# EDU_High-Speed-Design_CPU_Power.net
KiCad netlist of a schematic drawn in Altium Designer
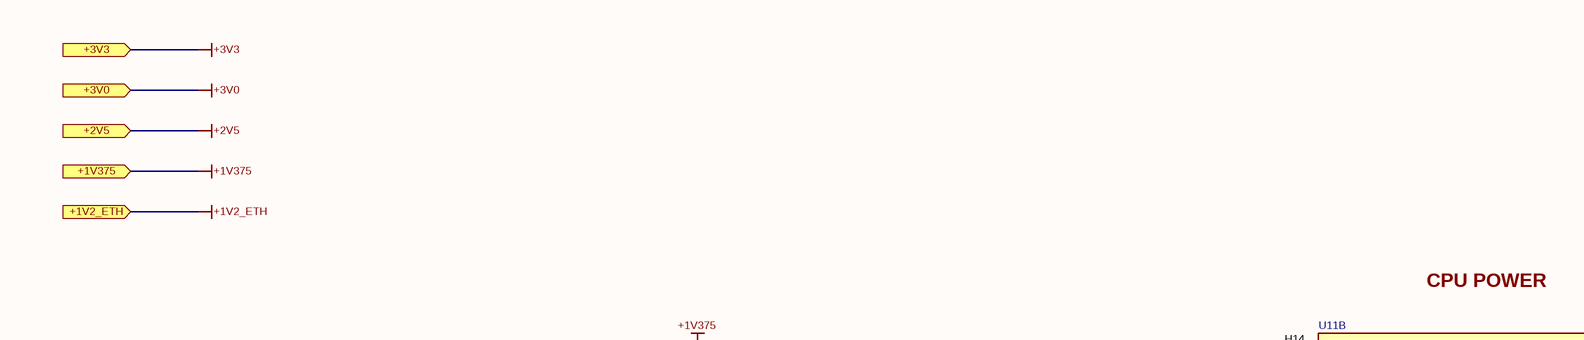
[diagram p0: EDU_High-Speed-Design_CPU_Power.SchDoc, top left]
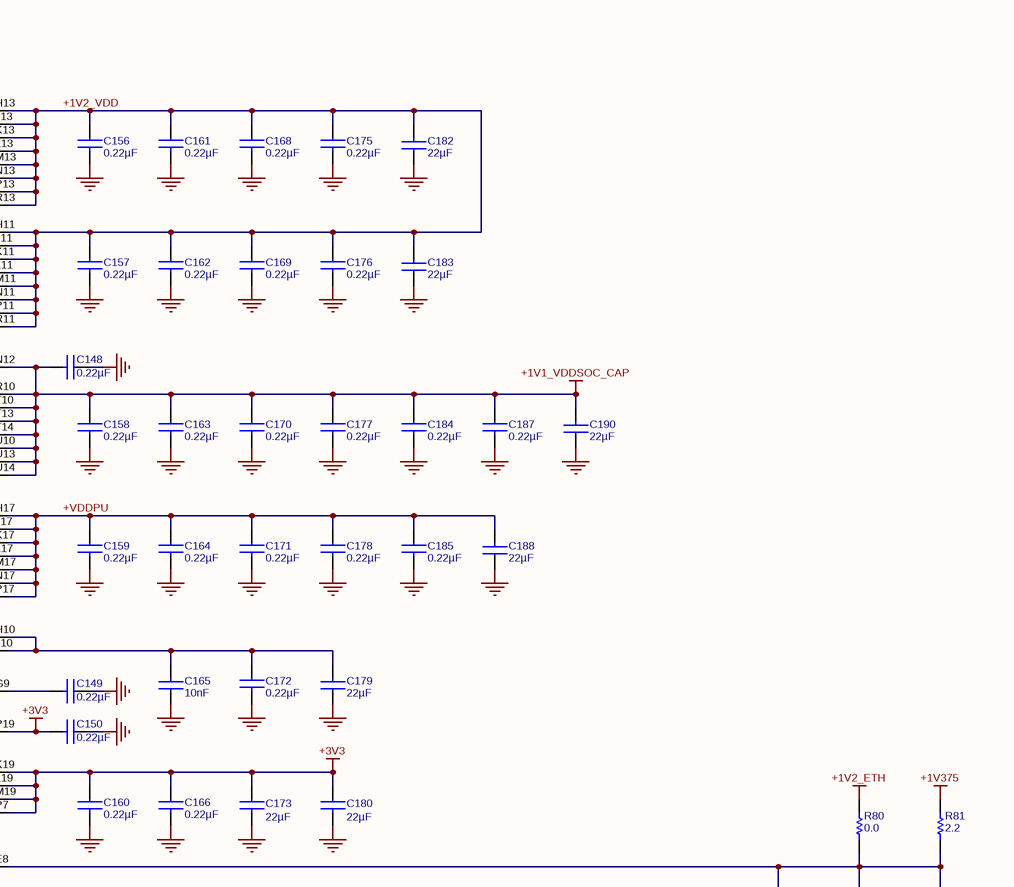
[diagram p1: EDU_High-Speed-Design_CPU_Power.SchDoc, top right]
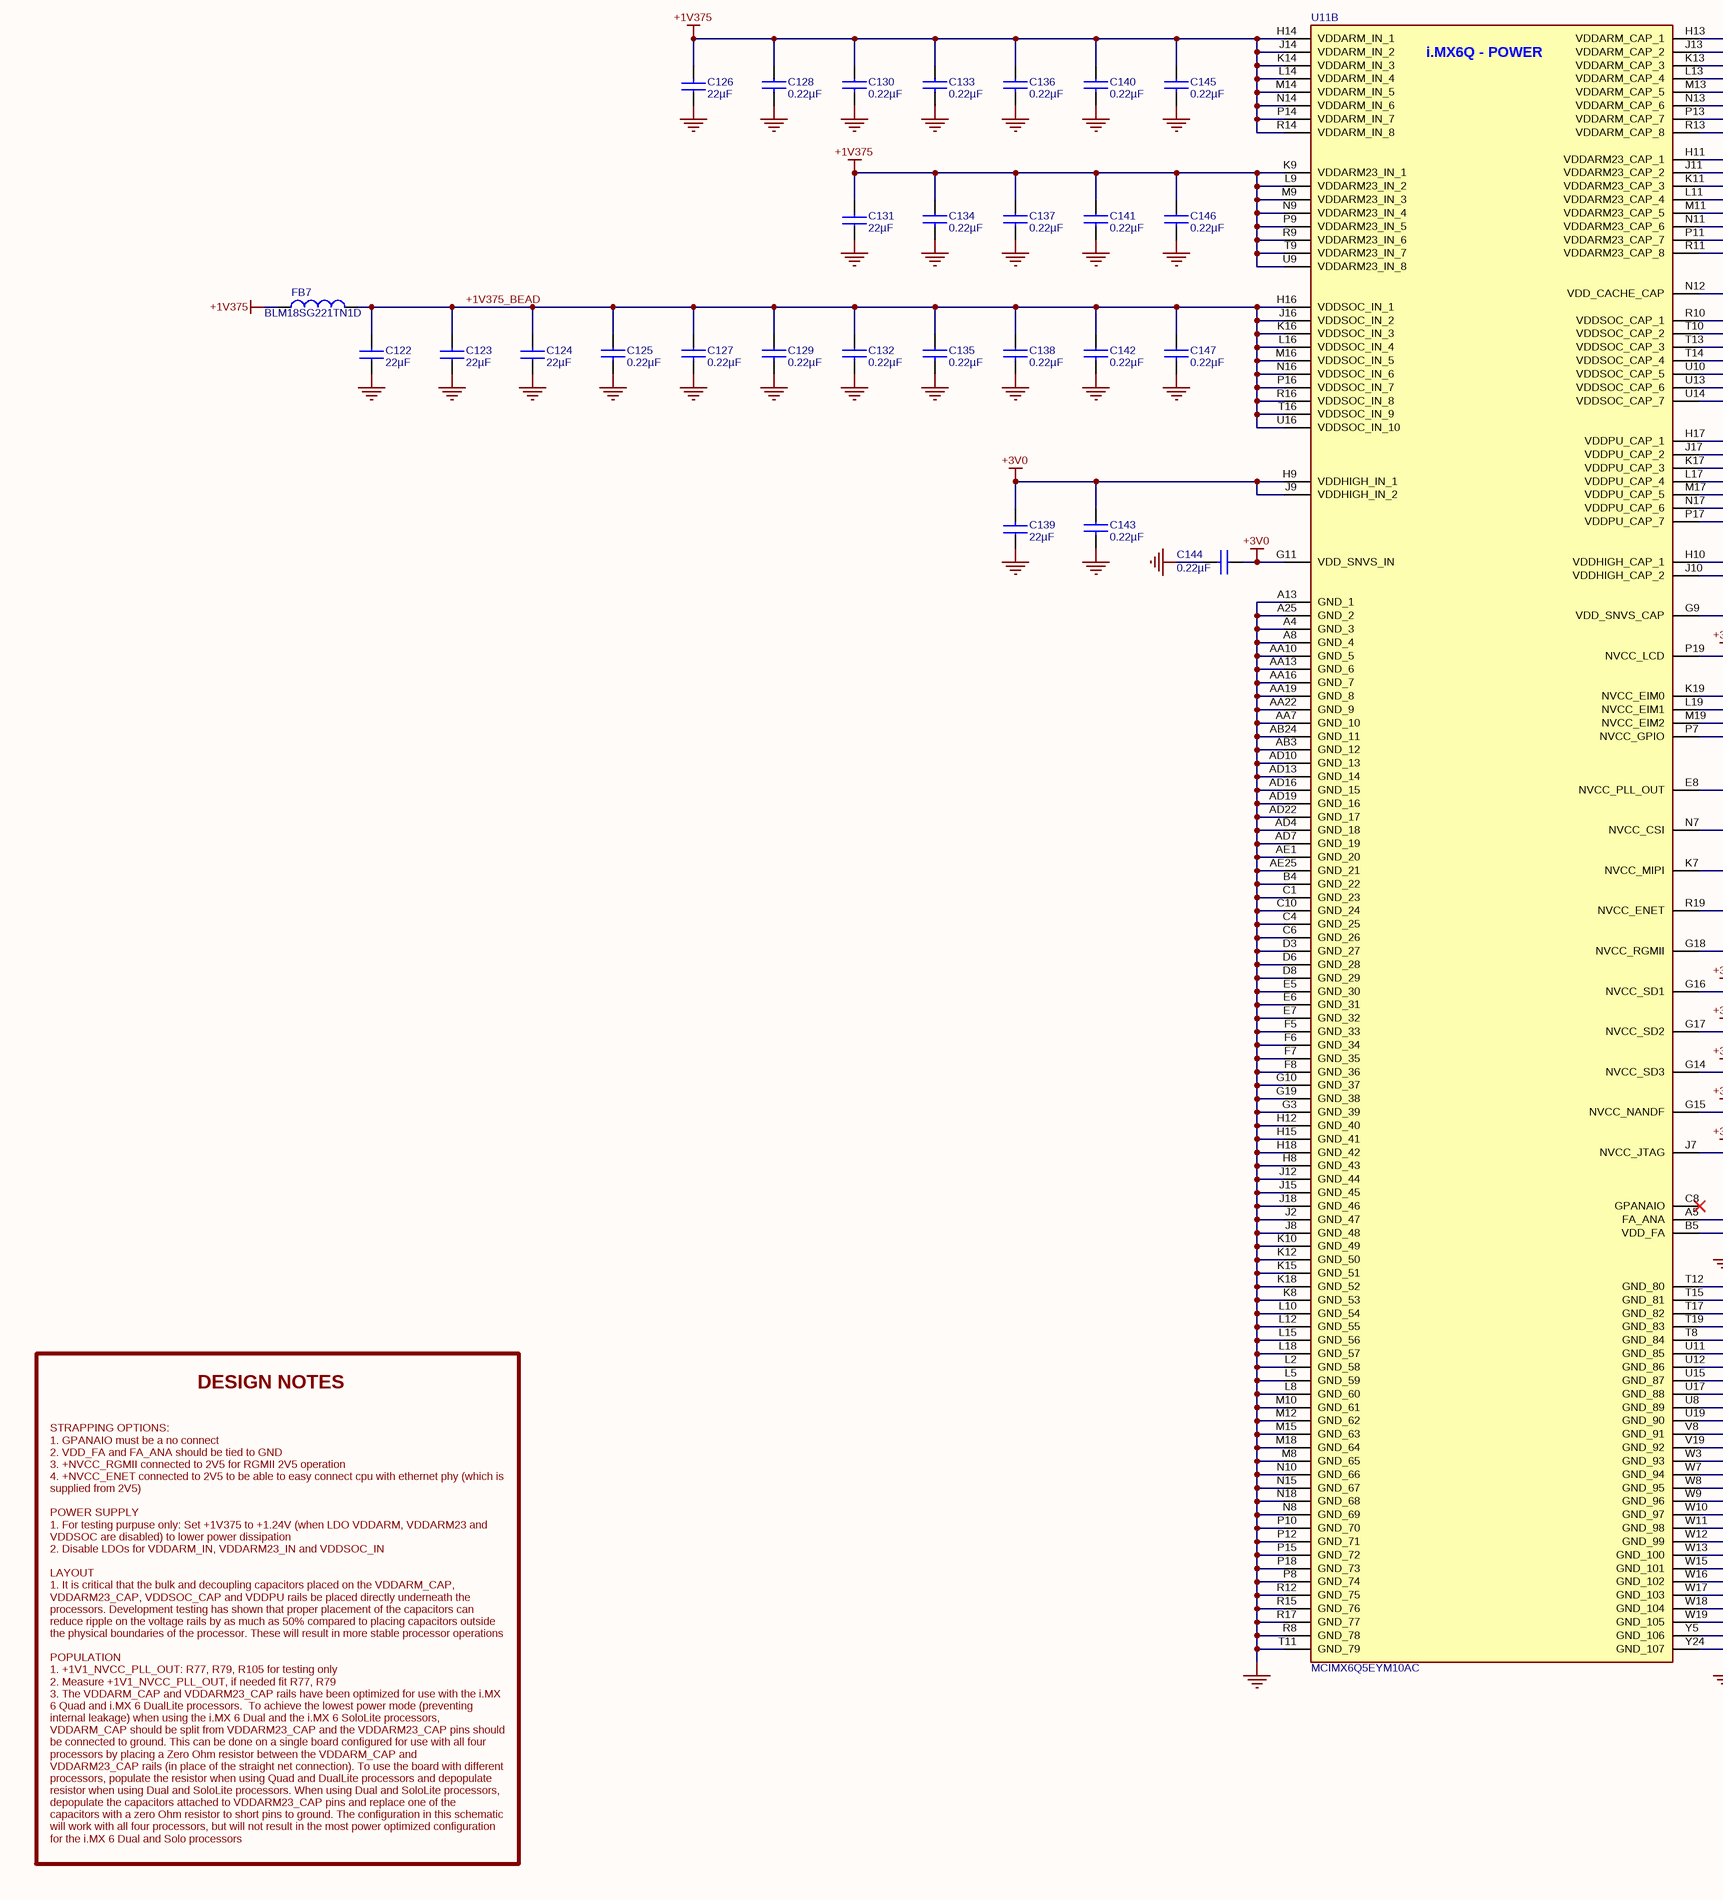
[diagram p2: EDU_High-Speed-Design_CPU_Power.SchDoc, bottom left]
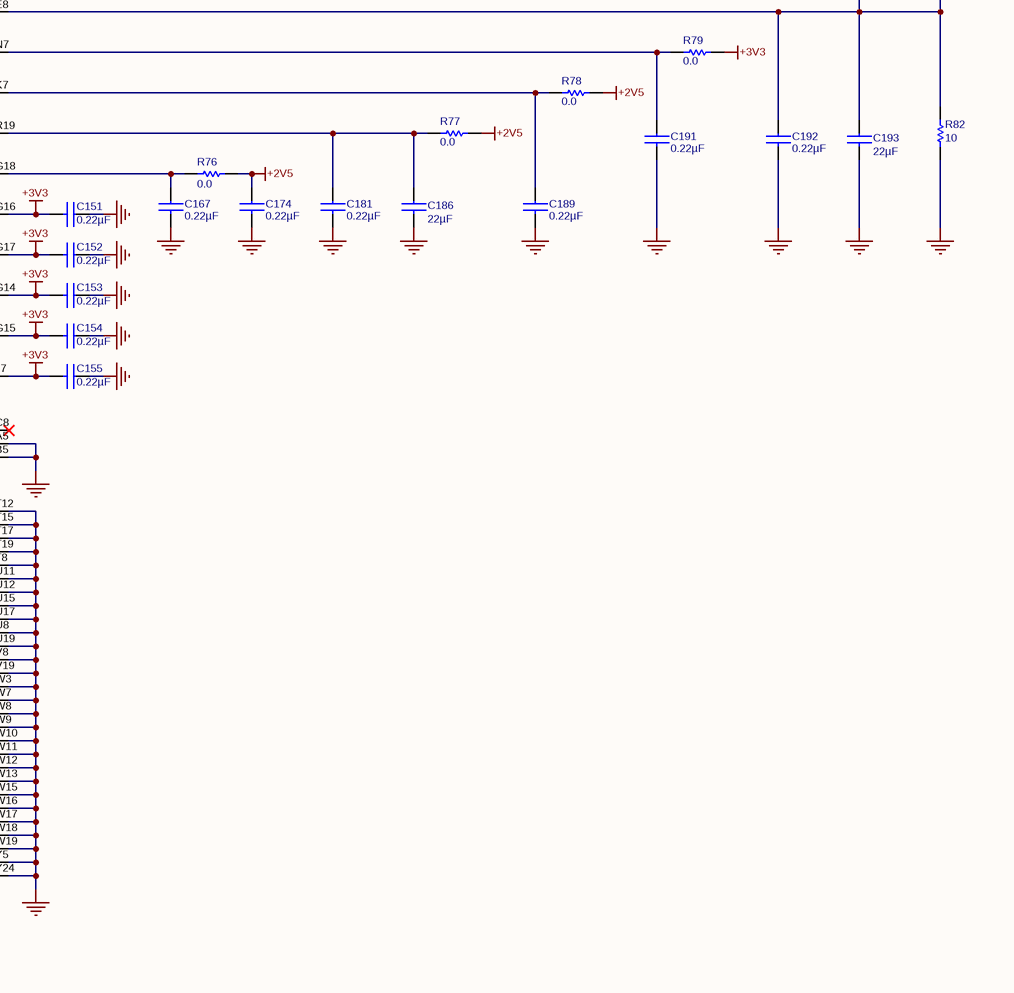
[diagram p3: EDU_High-Speed-Design_CPU_Power.SchDoc, bottom right]

(export (version "E")
  (design (tool "Eeschema 10.0.6"))
  (components
    (comp (ref "C122")
      (value "22µF")
      (footprint "C0603")
      (description "CAP CER 22UF 4V 20% X5R 0603")
      (fields (field (name "VOLTAGE") "4V"))
      (libsource (lib "EDU_High-Speed-Design") (part "GRM188R60G226MEA0L"))
    )
    (comp (ref "C123")
      (value "22µF")
      (footprint "C0603")
      (description "CAP CER 22UF 4V 20% X5R 0603")
      (fields (field (name "VOLTAGE") "4V"))
      (libsource (lib "EDU_High-Speed-Design") (part "GRM188R60G226MEA0L"))
    )
    (comp (ref "C124")
      (value "22µF")
      (footprint "C0603")
      (description "CAP CER 22UF 4V 20% X5R 0603")
      (fields (field (name "VOLTAGE") "4V"))
      (libsource (lib "EDU_High-Speed-Design") (part "GRM188R60G226MEA0L"))
    )
    (comp (ref "C125")
      (value "0.22µF")
      (footprint "C0402")
      (description "CAP CER .22UF 25V X5R 20% 0402")
      (fields (field (name "VOLTAGE") "25V"))
      (libsource (lib "EDU_High-Speed-Design") (part "C1005X5R1E224M"))
    )
    (comp (ref "C126")
      (value "22µF")
      (footprint "C0603")
      (description "CAP CER 22UF 4V 20% X5R 0603")
      (fields (field (name "VOLTAGE") "4V"))
      (libsource (lib "EDU_High-Speed-Design") (part "GRM188R60G226MEA0L"))
    )
    (comp (ref "C127")
      (value "0.22µF")
      (footprint "C0402")
      (description "CAP CER .22UF 25V X5R 20% 0402")
      (fields (field (name "VOLTAGE") "25V"))
      (libsource (lib "EDU_High-Speed-Design") (part "C1005X5R1E224M"))
    )
    (comp (ref "C128")
      (value "0.22µF")
      (footprint "C0402")
      (description "CAP CER .22UF 25V X5R 20% 0402")
      (fields (field (name "VOLTAGE") "25V"))
      (libsource (lib "EDU_High-Speed-Design") (part "C1005X5R1E224M"))
    )
    (comp (ref "C129")
      (value "0.22µF")
      (footprint "C0402")
      (description "CAP CER .22UF 25V X5R 20% 0402")
      (fields (field (name "VOLTAGE") "25V"))
      (libsource (lib "EDU_High-Speed-Design") (part "C1005X5R1E224M"))
    )
    (comp (ref "C130")
      (value "0.22µF")
      (footprint "C0402")
      (description "CAP CER .22UF 25V X5R 20% 0402")
      (fields (field (name "VOLTAGE") "25V"))
      (libsource (lib "EDU_High-Speed-Design") (part "C1005X5R1E224M"))
    )
    (comp (ref "C131")
      (value "22µF")
      (footprint "C0603")
      (description "CAP CER 22UF 4V 20% X5R 0603")
      (fields (field (name "VOLTAGE") "4V"))
      (libsource (lib "EDU_High-Speed-Design") (part "GRM188R60G226MEA0L"))
    )
    (comp (ref "C132")
      (value "0.22µF")
      (footprint "C0402")
      (description "CAP CER .22UF 25V X5R 20% 0402")
      (fields (field (name "VOLTAGE") "25V"))
      (libsource (lib "EDU_High-Speed-Design") (part "C1005X5R1E224M"))
    )
    (comp (ref "C133")
      (value "0.22µF")
      (footprint "C0402")
      (description "CAP CER .22UF 25V X5R 20% 0402")
      (fields (field (name "VOLTAGE") "25V"))
      (libsource (lib "EDU_High-Speed-Design") (part "C1005X5R1E224M"))
    )
    (comp (ref "C134")
      (value "0.22µF")
      (footprint "C0402")
      (description "CAP CER .22UF 25V X5R 20% 0402")
      (fields (field (name "VOLTAGE") "25V"))
      (libsource (lib "EDU_High-Speed-Design") (part "C1005X5R1E224M"))
    )
    (comp (ref "C135")
      (value "0.22µF")
      (footprint "C0402")
      (description "CAP CER .22UF 25V X5R 20% 0402")
      (fields (field (name "VOLTAGE") "25V"))
      (libsource (lib "EDU_High-Speed-Design") (part "C1005X5R1E224M"))
    )
    (comp (ref "C136")
      (value "0.22µF")
      (footprint "C0402")
      (description "CAP CER .22UF 25V X5R 20% 0402")
      (fields (field (name "VOLTAGE") "25V"))
      (libsource (lib "EDU_High-Speed-Design") (part "C1005X5R1E224M"))
    )
    (comp (ref "C137")
      (value "0.22µF")
      (footprint "C0402")
      (description "CAP CER .22UF 25V X5R 20% 0402")
      (fields (field (name "VOLTAGE") "25V"))
      (libsource (lib "EDU_High-Speed-Design") (part "C1005X5R1E224M"))
    )
    (comp (ref "C138")
      (value "0.22µF")
      (footprint "C0402")
      (description "CAP CER .22UF 25V X5R 20% 0402")
      (fields (field (name "VOLTAGE") "25V"))
      (libsource (lib "EDU_High-Speed-Design") (part "C1005X5R1E224M"))
    )
    (comp (ref "C139")
      (value "22µF")
      (footprint "C0603")
      (description "CAP CER 22UF 4V 20% X5R 0603")
      (fields (field (name "VOLTAGE") "4V"))
      (libsource (lib "EDU_High-Speed-Design") (part "GRM188R60G226MEA0L"))
    )
    (comp (ref "C140")
      (value "0.22µF")
      (footprint "C0402")
      (description "CAP CER .22UF 25V X5R 20% 0402")
      (fields (field (name "VOLTAGE") "25V"))
      (libsource (lib "EDU_High-Speed-Design") (part "C1005X5R1E224M"))
    )
    (comp (ref "C141")
      (value "0.22µF")
      (footprint "C0402")
      (description "CAP CER .22UF 25V X5R 20% 0402")
      (fields (field (name "VOLTAGE") "25V"))
      (libsource (lib "EDU_High-Speed-Design") (part "C1005X5R1E224M"))
    )
    (comp (ref "C142")
      (value "0.22µF")
      (footprint "C0402")
      (description "CAP CER .22UF 25V X5R 20% 0402")
      (fields (field (name "VOLTAGE") "25V"))
      (libsource (lib "EDU_High-Speed-Design") (part "C1005X5R1E224M"))
    )
    (comp (ref "C143")
      (value "0.22µF")
      (footprint "C0402")
      (description "CAP CER .22UF 25V X5R 20% 0402")
      (fields (field (name "VOLTAGE") "25V"))
      (libsource (lib "EDU_High-Speed-Design") (part "C1005X5R1E224M"))
    )
    (comp (ref "C144")
      (value "0.22µF")
      (footprint "C0402")
      (description "CAP CER .22UF 25V X5R 20% 0402")
      (fields (field (name "VOLTAGE") "25V"))
      (libsource (lib "EDU_High-Speed-Design") (part "C1005X5R1E224M"))
    )
    (comp (ref "C145")
      (value "0.22µF")
      (footprint "C0402")
      (description "CAP CER .22UF 25V X5R 20% 0402")
      (fields (field (name "VOLTAGE") "25V"))
      (libsource (lib "EDU_High-Speed-Design") (part "C1005X5R1E224M"))
    )
    (comp (ref "C146")
      (value "0.22µF")
      (footprint "C0402")
      (description "CAP CER .22UF 25V X5R 20% 0402")
      (fields (field (name "VOLTAGE") "25V"))
      (libsource (lib "EDU_High-Speed-Design") (part "C1005X5R1E224M"))
    )
    (comp (ref "C147")
      (value "0.22µF")
      (footprint "C0402")
      (description "CAP CER .22UF 25V X5R 20% 0402")
      (fields (field (name "VOLTAGE") "25V"))
      (libsource (lib "EDU_High-Speed-Design") (part "C1005X5R1E224M"))
    )
    (comp (ref "C148")
      (value "0.22µF")
      (footprint "C0402")
      (description "CAP CER .22UF 25V X5R 20% 0402")
      (fields (field (name "VOLTAGE") "25V"))
      (libsource (lib "EDU_High-Speed-Design") (part "C1005X5R1E224M"))
    )
    (comp (ref "C149")
      (value "0.22µF")
      (footprint "C0402")
      (description "CAP CER .22UF 25V X5R 20% 0402")
      (fields (field (name "VOLTAGE") "25V"))
      (libsource (lib "EDU_High-Speed-Design") (part "C1005X5R1E224M"))
    )
    (comp (ref "C150")
      (value "0.22µF")
      (footprint "C0402")
      (description "CAP CER .22UF 25V X5R 20% 0402")
      (fields (field (name "VOLTAGE") "25V"))
      (libsource (lib "EDU_High-Speed-Design") (part "C1005X5R1E224M"))
    )
    (comp (ref "C151")
      (value "0.22µF")
      (footprint "C0402")
      (description "CAP CER .22UF 25V X5R 20% 0402")
      (fields (field (name "VOLTAGE") "25V"))
      (libsource (lib "EDU_High-Speed-Design") (part "C1005X5R1E224M"))
    )
    (comp (ref "C152")
      (value "0.22µF")
      (footprint "C0402")
      (description "CAP CER .22UF 25V X5R 20% 0402")
      (fields (field (name "VOLTAGE") "25V"))
      (libsource (lib "EDU_High-Speed-Design") (part "C1005X5R1E224M"))
    )
    (comp (ref "C153")
      (value "0.22µF")
      (footprint "C0402")
      (description "CAP CER .22UF 25V X5R 20% 0402")
      (fields (field (name "VOLTAGE") "25V"))
      (libsource (lib "EDU_High-Speed-Design") (part "C1005X5R1E224M"))
    )
    (comp (ref "C154")
      (value "0.22µF")
      (footprint "C0402")
      (description "CAP CER .22UF 25V X5R 20% 0402")
      (fields (field (name "VOLTAGE") "25V"))
      (libsource (lib "EDU_High-Speed-Design") (part "C1005X5R1E224M"))
    )
    (comp (ref "C155")
      (value "0.22µF")
      (footprint "C0402")
      (description "CAP CER .22UF 25V X5R 20% 0402")
      (fields (field (name "VOLTAGE") "25V"))
      (libsource (lib "EDU_High-Speed-Design") (part "C1005X5R1E224M"))
    )
    (comp (ref "C156")
      (value "0.22µF")
      (footprint "C0402")
      (description "CAP CER .22UF 25V X5R 20% 0402")
      (fields (field (name "VOLTAGE") "25V"))
      (libsource (lib "EDU_High-Speed-Design") (part "C1005X5R1E224M"))
    )
    (comp (ref "C157")
      (value "0.22µF")
      (footprint "C0402")
      (description "CAP CER .22UF 25V X5R 20% 0402")
      (fields (field (name "VOLTAGE") "25V"))
      (libsource (lib "EDU_High-Speed-Design") (part "C1005X5R1E224M"))
    )
    (comp (ref "C158")
      (value "0.22µF")
      (footprint "C0402")
      (description "CAP CER .22UF 25V X5R 20% 0402")
      (fields (field (name "VOLTAGE") "25V"))
      (libsource (lib "EDU_High-Speed-Design") (part "C1005X5R1E224M"))
    )
    (comp (ref "C159")
      (value "0.22µF")
      (footprint "C0402")
      (description "CAP CER .22UF 25V X5R 20% 0402")
      (fields (field (name "VOLTAGE") "25V"))
      (libsource (lib "EDU_High-Speed-Design") (part "C1005X5R1E224M"))
    )
    (comp (ref "C160")
      (value "0.22µF")
      (footprint "C0402")
      (description "CAP CER .22UF 25V X5R 20% 0402")
      (fields (field (name "VOLTAGE") "25V"))
      (libsource (lib "EDU_High-Speed-Design") (part "C1005X5R1E224M"))
    )
    (comp (ref "C161")
      (value "0.22µF")
      (footprint "C0402")
      (description "CAP CER .22UF 25V X5R 20% 0402")
      (fields (field (name "VOLTAGE") "25V"))
      (libsource (lib "EDU_High-Speed-Design") (part "C1005X5R1E224M"))
    )
    (comp (ref "C162")
      (value "0.22µF")
      (footprint "C0402")
      (description "CAP CER .22UF 25V X5R 20% 0402")
      (fields (field (name "VOLTAGE") "25V"))
      (libsource (lib "EDU_High-Speed-Design") (part "C1005X5R1E224M"))
    )
    (comp (ref "C163")
      (value "0.22µF")
      (footprint "C0402")
      (description "CAP CER .22UF 25V X5R 20% 0402")
      (fields (field (name "VOLTAGE") "25V"))
      (libsource (lib "EDU_High-Speed-Design") (part "C1005X5R1E224M"))
    )
    (comp (ref "C164")
      (value "0.22µF")
      (footprint "C0402")
      (description "CAP CER .22UF 25V X5R 20% 0402")
      (fields (field (name "VOLTAGE") "25V"))
      (libsource (lib "EDU_High-Speed-Design") (part "C1005X5R1E224M"))
    )
    (comp (ref "C165")
      (value "10nF")
      (footprint "C0402")
      (description "CAP CER 10000PF 16V X7R 10% 0402")
      (fields
        (field (name "MANUFACTURER") "TDK Corporation")
        (field (name "MANUFACTURER PART NUMBER") "C1005X7R1C103K")
      )
      (libsource (lib "EDU_High-Speed-Design") (part "C1005X7R1C103K"))
    )
    (comp (ref "C166")
      (value "0.22µF")
      (footprint "C0402")
      (description "CAP CER .22UF 25V X5R 20% 0402")
      (fields (field (name "VOLTAGE") "25V"))
      (libsource (lib "EDU_High-Speed-Design") (part "C1005X5R1E224M"))
    )
    (comp (ref "C167")
      (value "0.22µF")
      (footprint "C0402")
      (description "CAP CER .22UF 25V X5R 20% 0402")
      (fields (field (name "VOLTAGE") "25V"))
      (libsource (lib "EDU_High-Speed-Design") (part "C1005X5R1E224M"))
    )
    (comp (ref "C168")
      (value "0.22µF")
      (footprint "C0402")
      (description "CAP CER .22UF 25V X5R 20% 0402")
      (fields (field (name "VOLTAGE") "25V"))
      (libsource (lib "EDU_High-Speed-Design") (part "C1005X5R1E224M"))
    )
    (comp (ref "C169")
      (value "0.22µF")
      (footprint "C0402")
      (description "CAP CER .22UF 25V X5R 20% 0402")
      (fields (field (name "VOLTAGE") "25V"))
      (libsource (lib "EDU_High-Speed-Design") (part "C1005X5R1E224M"))
    )
    (comp (ref "C170")
      (value "0.22µF")
      (footprint "C0402")
      (description "CAP CER .22UF 25V X5R 20% 0402")
      (fields (field (name "VOLTAGE") "25V"))
      (libsource (lib "EDU_High-Speed-Design") (part "C1005X5R1E224M"))
    )
    (comp (ref "C171")
      (value "0.22µF")
      (footprint "C0402")
      (description "CAP CER .22UF 25V X5R 20% 0402")
      (fields (field (name "VOLTAGE") "25V"))
      (libsource (lib "EDU_High-Speed-Design") (part "C1005X5R1E224M"))
    )
    (comp (ref "C172")
      (value "0.22µF")
      (footprint "C0402")
      (description "CAP CER .22UF 25V X5R 20% 0402")
      (fields (field (name "VOLTAGE") "25V"))
      (libsource (lib "EDU_High-Speed-Design") (part "C1005X5R1E224M"))
    )
    (comp (ref "C173")
      (value "22µF")
      (footprint "C0603")
      (description "CAP CER 22UF 4V 20% X5R 0603")
      (fields (field (name "VOLTAGE") "4V"))
      (libsource (lib "EDU_High-Speed-Design") (part "GRM188R60G226MEA0L"))
    )
    (comp (ref "C174")
      (value "0.22µF")
      (footprint "C0402")
      (description "CAP CER .22UF 25V X5R 20% 0402")
      (fields (field (name "VOLTAGE") "25V"))
      (libsource (lib "EDU_High-Speed-Design") (part "C1005X5R1E224M"))
    )
    (comp (ref "C175")
      (value "0.22µF")
      (footprint "C0402")
      (description "CAP CER .22UF 25V X5R 20% 0402")
      (fields (field (name "VOLTAGE") "25V"))
      (libsource (lib "EDU_High-Speed-Design") (part "C1005X5R1E224M"))
    )
    (comp (ref "C176")
      (value "0.22µF")
      (footprint "C0402")
      (description "CAP CER .22UF 25V X5R 20% 0402")
      (fields (field (name "VOLTAGE") "25V"))
      (libsource (lib "EDU_High-Speed-Design") (part "C1005X5R1E224M"))
    )
    (comp (ref "C177")
      (value "0.22µF")
      (footprint "C0402")
      (description "CAP CER .22UF 25V X5R 20% 0402")
      (fields (field (name "VOLTAGE") "25V"))
      (libsource (lib "EDU_High-Speed-Design") (part "C1005X5R1E224M"))
    )
    (comp (ref "C178")
      (value "0.22µF")
      (footprint "C0402")
      (description "CAP CER .22UF 25V X5R 20% 0402")
      (fields (field (name "VOLTAGE") "25V"))
      (libsource (lib "EDU_High-Speed-Design") (part "C1005X5R1E224M"))
    )
    (comp (ref "C179")
      (value "22µF")
      (footprint "C0603")
      (description "CAP CER 22UF 4V 20% X5R 0603")
      (fields (field (name "VOLTAGE") "4V"))
      (libsource (lib "EDU_High-Speed-Design") (part "GRM188R60G226MEA0L"))
    )
    (comp (ref "C180")
      (value "22µF")
      (footprint "C0603")
      (description "CAP CER 22UF 4V 20% X5R 0603")
      (fields (field (name "VOLTAGE") "4V"))
      (libsource (lib "EDU_High-Speed-Design") (part "GRM188R60G226MEA0L"))
    )
    (comp (ref "C181")
      (value "0.22µF")
      (footprint "C0402")
      (description "CAP CER .22UF 25V X5R 20% 0402")
      (fields (field (name "VOLTAGE") "25V"))
      (libsource (lib "EDU_High-Speed-Design") (part "C1005X5R1E224M"))
    )
    (comp (ref "C182")
      (value "22µF")
      (footprint "C0603")
      (description "CAP CER 22UF 4V 20% X5R 0603")
      (fields (field (name "VOLTAGE") "4V"))
      (libsource (lib "EDU_High-Speed-Design") (part "GRM188R60G226MEA0L"))
    )
    (comp (ref "C183")
      (value "22µF")
      (footprint "C0603")
      (description "CAP CER 22UF 4V 20% X5R 0603")
      (fields (field (name "VOLTAGE") "4V"))
      (libsource (lib "EDU_High-Speed-Design") (part "GRM188R60G226MEA0L"))
    )
    (comp (ref "C184")
      (value "0.22µF")
      (footprint "C0402")
      (description "CAP CER .22UF 25V X5R 20% 0402")
      (fields (field (name "VOLTAGE") "25V"))
      (libsource (lib "EDU_High-Speed-Design") (part "C1005X5R1E224M"))
    )
    (comp (ref "C185")
      (value "0.22µF")
      (footprint "C0402")
      (description "CAP CER .22UF 25V X5R 20% 0402")
      (fields (field (name "VOLTAGE") "25V"))
      (libsource (lib "EDU_High-Speed-Design") (part "C1005X5R1E224M"))
    )
    (comp (ref "C186")
      (value "22µF")
      (footprint "C0603")
      (description "CAP CER 22UF 4V 20% X5R 0603")
      (fields (field (name "VOLTAGE") "4V"))
      (libsource (lib "EDU_High-Speed-Design") (part "GRM188R60G226MEA0L"))
    )
    (comp (ref "C187")
      (value "0.22µF")
      (footprint "C0402")
      (description "CAP CER .22UF 25V X5R 20% 0402")
      (fields (field (name "VOLTAGE") "25V"))
      (libsource (lib "EDU_High-Speed-Design") (part "C1005X5R1E224M"))
    )
    (comp (ref "C188")
      (value "22µF")
      (footprint "C0603")
      (description "CAP CER 22UF 4V 20% X5R 0603")
      (fields (field (name "VOLTAGE") "4V"))
      (libsource (lib "EDU_High-Speed-Design") (part "GRM188R60G226MEA0L"))
    )
    (comp (ref "C189")
      (value "0.22µF")
      (footprint "C0402")
      (description "CAP CER .22UF 25V X5R 20% 0402")
      (fields (field (name "VOLTAGE") "25V"))
      (libsource (lib "EDU_High-Speed-Design") (part "C1005X5R1E224M"))
    )
    (comp (ref "C190")
      (value "22µF")
      (footprint "C0603")
      (description "CAP CER 22UF 4V 20% X5R 0603")
      (fields (field (name "VOLTAGE") "4V"))
      (libsource (lib "EDU_High-Speed-Design") (part "GRM188R60G226MEA0L"))
    )
    (comp (ref "C191")
      (value "0.22µF")
      (footprint "C0402")
      (description "CAP CER .22UF 25V X5R 20% 0402")
      (fields (field (name "VOLTAGE") "25V"))
      (libsource (lib "EDU_High-Speed-Design") (part "C1005X5R1E224M"))
    )
    (comp (ref "C192")
      (value "0.22µF")
      (footprint "C0402")
      (description "CAP CER .22UF 25V X5R 20% 0402")
      (fields (field (name "VOLTAGE") "25V"))
      (libsource (lib "EDU_High-Speed-Design") (part "C1005X5R1E224M"))
    )
    (comp (ref "C193")
      (value "22µF")
      (footprint "C0603")
      (description "CAP CER 22UF 4V 20% X5R 0603")
      (fields (field (name "VOLTAGE") "4V"))
      (libsource (lib "EDU_High-Speed-Design") (part "GRM188R60G226MEA0L"))
    )
    (comp (ref "FB7")
      (value "BLM18SG221TN1D")
      (footprint "L0603")
      (description "FERRITE CHIP 220 OHM 2500MA 0603")
      (libsource (lib "EDU_High-Speed-Design") (part "BLM18SG221TN1D"))
    )
    (comp (ref "R76")
      (value "0.0")
      (footprint "R0402")
      (description "RES 0.0 OHM 1/16W 0402 SMD")
      (libsource (lib "EDU_High-Speed-Design") (part "RC0402JR-070RL"))
    )
    (comp (ref "R77")
      (value "0.0")
      (footprint "R0402")
      (description "RES 0.0 OHM 1/16W 0402 SMD")
      (libsource (lib "EDU_High-Speed-Design") (part "RC0402JR-070RL"))
    )
    (comp (ref "R78")
      (value "0.0")
      (footprint "R0402")
      (description "RES 0.0 OHM 1/16W 0402 SMD")
      (libsource (lib "EDU_High-Speed-Design") (part "RC0402JR-070RL"))
    )
    (comp (ref "R79")
      (value "0.0")
      (footprint "R0402")
      (description "RES 0.0 OHM 1/16W 0402 SMD")
      (libsource (lib "EDU_High-Speed-Design") (part "RC0402JR-070RL"))
    )
    (comp (ref "R80")
      (value "0.0")
      (footprint "R0402")
      (description "RES 0.0 OHM 1/16W 0402 SMD")
      (libsource (lib "EDU_High-Speed-Design") (part "RC0402JR-070RL"))
    )
    (comp (ref "R81")
      (value "2.2")
      (footprint "R0402")
      (description "RES 2.20 OHM 1/16W 1% 0402 SMD")
      (libsource (lib "EDU_High-Speed-Design") (part "CRCW04022R20FKED"))
    )
    (comp (ref "R82")
      (value "10")
      (footprint "R0402")
      (description "RES 10.0 OHM 1/16W 1% 0402 SMD")
      (libsource (lib "EDU_High-Speed-Design") (part "RC0402FR-0710RL"))
    )
    (comp (ref "U11")
      (value "MCIMX6Q5EYM10AC")
      (footprint "MCIMX6Q5EYM10AC")
      (description "IC MCU 32BIT ARM QUAD 624FCBGA")
      (libsource (lib "EDU_High-Speed-Design") (part "MCIMX6Q5EYM10AC"))
    )
  )
  (nets
    (net (code "1") (name "+1V1_VDDSOC_CAP") (class "Default")
      (node (ref "C148") (pin "2") (pinfunction "2_2") (pintype "passive"))
      (node (ref "C158") (pin "1") (pinfunction "1_1") (pintype "passive"))
      (node (ref "C163") (pin "1") (pinfunction "1_1") (pintype "passive"))
      (node (ref "C170") (pin "1") (pinfunction "1_1") (pintype "passive"))
      (node (ref "C177") (pin "1") (pinfunction "1_1") (pintype "passive"))
      (node (ref "C184") (pin "1") (pinfunction "1_1") (pintype "passive"))
      (node (ref "C187") (pin "1") (pinfunction "1_1") (pintype "passive"))
      (node (ref "C190") (pin "2") (pinfunction "2_2") (pintype "passive"))
      (node (ref "U11") (pin "N12") (pinfunction "VDD_CACHE_CAP_N12") (pintype "passive"))
      (node (ref "U11") (pin "R10") (pinfunction "VDDSOC_CAP_1_R10") (pintype "passive"))
      (node (ref "U11") (pin "T10") (pinfunction "VDDSOC_CAP_2_T10") (pintype "passive"))
      (node (ref "U11") (pin "T13") (pinfunction "VDDSOC_CAP_3_T13") (pintype "passive"))
      (node (ref "U11") (pin "T14") (pinfunction "VDDSOC_CAP_4_T14") (pintype "passive"))
      (node (ref "U11") (pin "U10") (pinfunction "VDDSOC_CAP_5_U10") (pintype "passive"))
      (node (ref "U11") (pin "U13") (pinfunction "VDDSOC_CAP_6_U13") (pintype "passive"))
      (node (ref "U11") (pin "U14") (pinfunction "VDDSOC_CAP_7_U14") (pintype "passive"))
    )
    (net (code "2") (name "+1V2_ETH") (class "Default")
      (node (ref "R80") (pin "1") (pinfunction "1_1") (pintype "passive"))
    )
    (net (code "3") (name "+1V375") (class "Default")
      (node (ref "C126") (pin "2") (pinfunction "2_2") (pintype "passive"))
      (node (ref "C128") (pin "1") (pinfunction "1_1") (pintype "passive"))
      (node (ref "C130") (pin "1") (pinfunction "1_1") (pintype "passive"))
      (node (ref "C131") (pin "2") (pinfunction "2_2") (pintype "passive"))
      (node (ref "C133") (pin "1") (pinfunction "1_1") (pintype "passive"))
      (node (ref "C134") (pin "1") (pinfunction "1_1") (pintype "passive"))
      (node (ref "C136") (pin "1") (pinfunction "1_1") (pintype "passive"))
      (node (ref "C137") (pin "1") (pinfunction "1_1") (pintype "passive"))
      (node (ref "C140") (pin "1") (pinfunction "1_1") (pintype "passive"))
      (node (ref "C141") (pin "1") (pinfunction "1_1") (pintype "passive"))
      (node (ref "C145") (pin "1") (pinfunction "1_1") (pintype "passive"))
      (node (ref "C146") (pin "1") (pinfunction "1_1") (pintype "passive"))
      (node (ref "FB7") (pin "1") (pinfunction "1_1") (pintype "passive"))
      (node (ref "R81") (pin "2") (pinfunction "2_2") (pintype "passive"))
      (node (ref "U11") (pin "H14") (pinfunction "VDDARM_IN_1_H14") (pintype "passive"))
      (node (ref "U11") (pin "J14") (pinfunction "VDDARM_IN_2_J14") (pintype "passive"))
      (node (ref "U11") (pin "K14") (pinfunction "VDDARM_IN_3_K14") (pintype "passive"))
      (node (ref "U11") (pin "K9") (pinfunction "VDDARM23_IN_1_K9") (pintype "passive"))
      (node (ref "U11") (pin "L14") (pinfunction "VDDARM_IN_4_L14") (pintype "passive"))
      (node (ref "U11") (pin "L9") (pinfunction "VDDARM23_IN_2_L9") (pintype "passive"))
      (node (ref "U11") (pin "M14") (pinfunction "VDDARM_IN_5_M14") (pintype "passive"))
      (node (ref "U11") (pin "M9") (pinfunction "VDDARM23_IN_3_M9") (pintype "passive"))
      (node (ref "U11") (pin "N14") (pinfunction "VDDARM_IN_6_N14") (pintype "passive"))
      (node (ref "U11") (pin "N9") (pinfunction "VDDARM23_IN_4_N9") (pintype "passive"))
      (node (ref "U11") (pin "P14") (pinfunction "VDDARM_IN_7_P14") (pintype "passive"))
      (node (ref "U11") (pin "P9") (pinfunction "VDDARM23_IN_5_P9") (pintype "passive"))
      (node (ref "U11") (pin "R14") (pinfunction "VDDARM_IN_8_R14") (pintype "passive"))
      (node (ref "U11") (pin "R9") (pinfunction "VDDARM23_IN_6_R9") (pintype "passive"))
      (node (ref "U11") (pin "T9") (pinfunction "VDDARM23_IN_7_T9") (pintype "passive"))
      (node (ref "U11") (pin "U9") (pinfunction "VDDARM23_IN_8_U9") (pintype "passive"))
    )
    (net (code "4") (name "+2V5") (class "Default")
      (node (ref "C174") (pin "1") (pinfunction "1_1") (pintype "passive"))
      (node (ref "R76") (pin "1") (pinfunction "1_1") (pintype "passive"))
      (node (ref "R77") (pin "2") (pinfunction "2_2") (pintype "passive"))
      (node (ref "R78") (pin "2") (pinfunction "2_2") (pintype "passive"))
    )
    (net (code "5") (name "+3V0") (class "Default")
      (node (ref "C139") (pin "2") (pinfunction "2_2") (pintype "passive"))
      (node (ref "C143") (pin "1") (pinfunction "1_1") (pintype "passive"))
      (node (ref "C144") (pin "1") (pinfunction "1_1") (pintype "passive"))
      (node (ref "U11") (pin "G11") (pinfunction "VDD_SNVS_IN_G11") (pintype "passive"))
      (node (ref "U11") (pin "H9") (pinfunction "VDDHIGH_IN_1_H9") (pintype "passive"))
      (node (ref "U11") (pin "J9") (pinfunction "VDDHIGH_IN_2_J9") (pintype "passive"))
    )
    (net (code "6") (name "+3V3") (class "Default")
      (node (ref "C150") (pin "2") (pinfunction "2_2") (pintype "passive"))
      (node (ref "C151") (pin "2") (pinfunction "2_2") (pintype "passive"))
      (node (ref "C152") (pin "2") (pinfunction "2_2") (pintype "passive"))
      (node (ref "C153") (pin "2") (pinfunction "2_2") (pintype "passive"))
      (node (ref "C154") (pin "2") (pinfunction "2_2") (pintype "passive"))
      (node (ref "C155") (pin "2") (pinfunction "2_2") (pintype "passive"))
      (node (ref "C160") (pin "1") (pinfunction "1_1") (pintype "passive"))
      (node (ref "C166") (pin "1") (pinfunction "1_1") (pintype "passive"))
      (node (ref "C173") (pin "1") (pinfunction "1_1") (pintype "passive"))
      (node (ref "C180") (pin "1") (pinfunction "1_1") (pintype "passive"))
      (node (ref "R79") (pin "2") (pinfunction "2_2") (pintype "passive"))
      (node (ref "U11") (pin "G14") (pinfunction "NVCC_SD3_G14") (pintype "passive"))
      (node (ref "U11") (pin "G15") (pinfunction "NVCC_NANDF_G15") (pintype "passive"))
      (node (ref "U11") (pin "G16") (pinfunction "NVCC_SD1_G16") (pintype "passive"))
      (node (ref "U11") (pin "G17") (pinfunction "NVCC_SD2_G17") (pintype "passive"))
      (node (ref "U11") (pin "J7") (pinfunction "NVCC_JTAG_J7") (pintype "passive"))
      (node (ref "U11") (pin "K19") (pinfunction "NVCC_EIM0_K19") (pintype "passive"))
      (node (ref "U11") (pin "L19") (pinfunction "NVCC_EIM1_L19") (pintype "passive"))
      (node (ref "U11") (pin "M19") (pinfunction "NVCC_EIM2_M19") (pintype "passive"))
      (node (ref "U11") (pin "P19") (pinfunction "NVCC_LCD_P19") (pintype "passive"))
      (node (ref "U11") (pin "P7") (pinfunction "NVCC_GPIO_P7") (pintype "passive"))
    )
    (net (code "7") (name "/+1V2_VDD") (class "Default")
      (node (ref "C156") (pin "1") (pinfunction "1_1") (pintype "passive"))
      (node (ref "C157") (pin "1") (pinfunction "1_1") (pintype "passive"))
      (node (ref "C161") (pin "1") (pinfunction "1_1") (pintype "passive"))
      (node (ref "C162") (pin "1") (pinfunction "1_1") (pintype "passive"))
      (node (ref "C168") (pin "1") (pinfunction "1_1") (pintype "passive"))
      (node (ref "C169") (pin "1") (pinfunction "1_1") (pintype "passive"))
      (node (ref "C175") (pin "1") (pinfunction "1_1") (pintype "passive"))
      (node (ref "C176") (pin "1") (pinfunction "1_1") (pintype "passive"))
      (node (ref "C182") (pin "2") (pinfunction "2_2") (pintype "passive"))
      (node (ref "C183") (pin "2") (pinfunction "2_2") (pintype "passive"))
      (node (ref "U11") (pin "H11") (pinfunction "VDDARM23_CAP_1_H11") (pintype "passive"))
      (node (ref "U11") (pin "H13") (pinfunction "VDDARM_CAP_1_H13") (pintype "passive"))
      (node (ref "U11") (pin "J11") (pinfunction "VDDARM23_CAP_2_J11") (pintype "passive"))
      (node (ref "U11") (pin "J13") (pinfunction "VDDARM_CAP_2_J13") (pintype "passive"))
      (node (ref "U11") (pin "K11") (pinfunction "VDDARM23_CAP_3_K11") (pintype "passive"))
      (node (ref "U11") (pin "K13") (pinfunction "VDDARM_CAP_3_K13") (pintype "passive"))
      (node (ref "U11") (pin "L11") (pinfunction "VDDARM23_CAP_4_L11") (pintype "passive"))
      (node (ref "U11") (pin "L13") (pinfunction "VDDARM_CAP_4_L13") (pintype "passive"))
      (node (ref "U11") (pin "M11") (pinfunction "VDDARM23_CAP_5_M11") (pintype "passive"))
      (node (ref "U11") (pin "M13") (pinfunction "VDDARM_CAP_5_M13") (pintype "passive"))
      (node (ref "U11") (pin "N11") (pinfunction "VDDARM23_CAP_6_N11") (pintype "passive"))
      (node (ref "U11") (pin "N13") (pinfunction "VDDARM_CAP_6_N13") (pintype "passive"))
      (node (ref "U11") (pin "P11") (pinfunction "VDDARM23_CAP_7_P11") (pintype "passive"))
      (node (ref "U11") (pin "P13") (pinfunction "VDDARM_CAP_7_P13") (pintype "passive"))
      (node (ref "U11") (pin "R11") (pinfunction "VDDARM23_CAP_8_R11") (pintype "passive"))
      (node (ref "U11") (pin "R13") (pinfunction "VDDARM_CAP_8_R13") (pintype "passive"))
    )
    (net (code "8") (name "/+1V375_BEAD") (class "Default")
      (node (ref "C122") (pin "2") (pinfunction "2_2") (pintype "passive"))
      (node (ref "C123") (pin "2") (pinfunction "2_2") (pintype "passive"))
      (node (ref "C124") (pin "2") (pinfunction "2_2") (pintype "passive"))
      (node (ref "C125") (pin "1") (pinfunction "1_1") (pintype "passive"))
      (node (ref "C127") (pin "1") (pinfunction "1_1") (pintype "passive"))
      (node (ref "C129") (pin "1") (pinfunction "1_1") (pintype "passive"))
      (node (ref "C132") (pin "1") (pinfunction "1_1") (pintype "passive"))
      (node (ref "C135") (pin "1") (pinfunction "1_1") (pintype "passive"))
      (node (ref "C138") (pin "1") (pinfunction "1_1") (pintype "passive"))
      (node (ref "C142") (pin "1") (pinfunction "1_1") (pintype "passive"))
      (node (ref "C147") (pin "1") (pinfunction "1_1") (pintype "passive"))
      (node (ref "FB7") (pin "2") (pinfunction "2_2") (pintype "passive"))
      (node (ref "U11") (pin "H16") (pinfunction "VDDSOC_IN_1_H16") (pintype "passive"))
      (node (ref "U11") (pin "J16") (pinfunction "VDDSOC_IN_2_J16") (pintype "passive"))
      (node (ref "U11") (pin "K16") (pinfunction "VDDSOC_IN_3_K16") (pintype "passive"))
      (node (ref "U11") (pin "L16") (pinfunction "VDDSOC_IN_4_L16") (pintype "passive"))
      (node (ref "U11") (pin "M16") (pinfunction "VDDSOC_IN_5_M16") (pintype "passive"))
      (node (ref "U11") (pin "N16") (pinfunction "VDDSOC_IN_6_N16") (pintype "passive"))
      (node (ref "U11") (pin "P16") (pinfunction "VDDSOC_IN_7_P16") (pintype "passive"))
      (node (ref "U11") (pin "R16") (pinfunction "VDDSOC_IN_8_R16") (pintype "passive"))
      (node (ref "U11") (pin "T16") (pinfunction "VDDSOC_IN_9_T16") (pintype "passive"))
      (node (ref "U11") (pin "U16") (pinfunction "VDDSOC_IN_10_U16") (pintype "passive"))
    )
    (net (code "9") (name "/+VDDPU") (class "Default")
      (node (ref "C159") (pin "1") (pinfunction "1_1") (pintype "passive"))
      (node (ref "C164") (pin "1") (pinfunction "1_1") (pintype "passive"))
      (node (ref "C171") (pin "1") (pinfunction "1_1") (pintype "passive"))
      (node (ref "C178") (pin "1") (pinfunction "1_1") (pintype "passive"))
      (node (ref "C185") (pin "1") (pinfunction "1_1") (pintype "passive"))
      (node (ref "C188") (pin "2") (pinfunction "2_2") (pintype "passive"))
      (node (ref "U11") (pin "H17") (pinfunction "VDDPU_CAP_1_H17") (pintype "passive"))
      (node (ref "U11") (pin "J17") (pinfunction "VDDPU_CAP_2_J17") (pintype "passive"))
      (node (ref "U11") (pin "K17") (pinfunction "VDDPU_CAP_3_K17") (pintype "passive"))
      (node (ref "U11") (pin "L17") (pinfunction "VDDPU_CAP_4_L17") (pintype "passive"))
      (node (ref "U11") (pin "M17") (pinfunction "VDDPU_CAP_5_M17") (pintype "passive"))
      (node (ref "U11") (pin "N17") (pinfunction "VDDPU_CAP_6_N17") (pintype "passive"))
      (node (ref "U11") (pin "P17") (pinfunction "VDDPU_CAP_7_P17") (pintype "passive"))
    )
    (net (code "10") (name "GND") (class "Default")
      (node (ref "C122") (pin "1") (pinfunction "1_1") (pintype "passive"))
      (node (ref "C123") (pin "1") (pinfunction "1_1") (pintype "passive"))
      (node (ref "C124") (pin "1") (pinfunction "1_1") (pintype "passive"))
      (node (ref "C125") (pin "2") (pinfunction "2_2") (pintype "passive"))
      (node (ref "C126") (pin "1") (pinfunction "1_1") (pintype "passive"))
      (node (ref "C127") (pin "2") (pinfunction "2_2") (pintype "passive"))
      (node (ref "C128") (pin "2") (pinfunction "2_2") (pintype "passive"))
      (node (ref "C129") (pin "2") (pinfunction "2_2") (pintype "passive"))
      (node (ref "C130") (pin "2") (pinfunction "2_2") (pintype "passive"))
      (node (ref "C131") (pin "1") (pinfunction "1_1") (pintype "passive"))
      (node (ref "C132") (pin "2") (pinfunction "2_2") (pintype "passive"))
      (node (ref "C133") (pin "2") (pinfunction "2_2") (pintype "passive"))
      (node (ref "C134") (pin "2") (pinfunction "2_2") (pintype "passive"))
      (node (ref "C135") (pin "2") (pinfunction "2_2") (pintype "passive"))
      (node (ref "C136") (pin "2") (pinfunction "2_2") (pintype "passive"))
      (node (ref "C137") (pin "2") (pinfunction "2_2") (pintype "passive"))
      (node (ref "C138") (pin "2") (pinfunction "2_2") (pintype "passive"))
      (node (ref "C139") (pin "1") (pinfunction "1_1") (pintype "passive"))
      (node (ref "C140") (pin "2") (pinfunction "2_2") (pintype "passive"))
      (node (ref "C141") (pin "2") (pinfunction "2_2") (pintype "passive"))
      (node (ref "C142") (pin "2") (pinfunction "2_2") (pintype "passive"))
      (node (ref "C143") (pin "2") (pinfunction "2_2") (pintype "passive"))
      (node (ref "C144") (pin "2") (pinfunction "2_2") (pintype "passive"))
      (node (ref "C145") (pin "2") (pinfunction "2_2") (pintype "passive"))
      (node (ref "C146") (pin "2") (pinfunction "2_2") (pintype "passive"))
      (node (ref "C147") (pin "2") (pinfunction "2_2") (pintype "passive"))
      (node (ref "C148") (pin "1") (pinfunction "1_1") (pintype "passive"))
      (node (ref "C149") (pin "1") (pinfunction "1_1") (pintype "passive"))
      (node (ref "C150") (pin "1") (pinfunction "1_1") (pintype "passive"))
      (node (ref "C151") (pin "1") (pinfunction "1_1") (pintype "passive"))
      (node (ref "C152") (pin "1") (pinfunction "1_1") (pintype "passive"))
      (node (ref "C153") (pin "1") (pinfunction "1_1") (pintype "passive"))
      (node (ref "C154") (pin "1") (pinfunction "1_1") (pintype "passive"))
      (node (ref "C155") (pin "1") (pinfunction "1_1") (pintype "passive"))
      (node (ref "C156") (pin "2") (pinfunction "2_2") (pintype "passive"))
      (node (ref "C157") (pin "2") (pinfunction "2_2") (pintype "passive"))
      (node (ref "C158") (pin "2") (pinfunction "2_2") (pintype "passive"))
      (node (ref "C159") (pin "2") (pinfunction "2_2") (pintype "passive"))
      (node (ref "C160") (pin "2") (pinfunction "2_2") (pintype "passive"))
      (node (ref "C161") (pin "2") (pinfunction "2_2") (pintype "passive"))
      (node (ref "C162") (pin "2") (pinfunction "2_2") (pintype "passive"))
      (node (ref "C163") (pin "2") (pinfunction "2_2") (pintype "passive"))
      (node (ref "C164") (pin "2") (pinfunction "2_2") (pintype "passive"))
      (node (ref "C165") (pin "1") (pinfunction "1_1") (pintype "passive"))
      (node (ref "C166") (pin "2") (pinfunction "2_2") (pintype "passive"))
      (node (ref "C167") (pin "2") (pinfunction "2_2") (pintype "passive"))
      (node (ref "C168") (pin "2") (pinfunction "2_2") (pintype "passive"))
      (node (ref "C169") (pin "2") (pinfunction "2_2") (pintype "passive"))
      (node (ref "C170") (pin "2") (pinfunction "2_2") (pintype "passive"))
      (node (ref "C171") (pin "2") (pinfunction "2_2") (pintype "passive"))
      (node (ref "C172") (pin "2") (pinfunction "2_2") (pintype "passive"))
      (node (ref "C173") (pin "2") (pinfunction "2_2") (pintype "passive"))
      (node (ref "C174") (pin "2") (pinfunction "2_2") (pintype "passive"))
      (node (ref "C175") (pin "2") (pinfunction "2_2") (pintype "passive"))
      (node (ref "C176") (pin "2") (pinfunction "2_2") (pintype "passive"))
      (node (ref "C177") (pin "2") (pinfunction "2_2") (pintype "passive"))
      (node (ref "C178") (pin "2") (pinfunction "2_2") (pintype "passive"))
      (node (ref "C179") (pin "1") (pinfunction "1_1") (pintype "passive"))
      (node (ref "C180") (pin "2") (pinfunction "2_2") (pintype "passive"))
      (node (ref "C181") (pin "2") (pinfunction "2_2") (pintype "passive"))
      (node (ref "C182") (pin "1") (pinfunction "1_1") (pintype "passive"))
      (node (ref "C183") (pin "1") (pinfunction "1_1") (pintype "passive"))
      (node (ref "C184") (pin "2") (pinfunction "2_2") (pintype "passive"))
      (node (ref "C185") (pin "2") (pinfunction "2_2") (pintype "passive"))
      (node (ref "C186") (pin "2") (pinfunction "2_2") (pintype "passive"))
      (node (ref "C187") (pin "2") (pinfunction "2_2") (pintype "passive"))
      (node (ref "C188") (pin "1") (pinfunction "1_1") (pintype "passive"))
      (node (ref "C189") (pin "2") (pinfunction "2_2") (pintype "passive"))
      (node (ref "C190") (pin "1") (pinfunction "1_1") (pintype "passive"))
      (node (ref "C191") (pin "2") (pinfunction "2_2") (pintype "passive"))
      (node (ref "C192") (pin "2") (pinfunction "2_2") (pintype "passive"))
      (node (ref "C193") (pin "2") (pinfunction "2_2") (pintype "passive"))
      (node (ref "R82") (pin "2") (pinfunction "2_2") (pintype "passive"))
      (node (ref "U11") (pin "A13") (pinfunction "GND_1_A13") (pintype "passive"))
      (node (ref "U11") (pin "A25") (pinfunction "GND_2_A25") (pintype "passive"))
      (node (ref "U11") (pin "A4") (pinfunction "GND_3_A4") (pintype "passive"))
      (node (ref "U11") (pin "A5") (pinfunction "FA_ANA_A5") (pintype "passive"))
      (node (ref "U11") (pin "A8") (pinfunction "GND_4_A8") (pintype "passive"))
      (node (ref "U11") (pin "AA10") (pinfunction "GND_5_AA10") (pintype "passive"))
      (node (ref "U11") (pin "AA13") (pinfunction "GND_6_AA13") (pintype "passive"))
      (node (ref "U11") (pin "AA16") (pinfunction "GND_7_AA16") (pintype "passive"))
      (node (ref "U11") (pin "AA19") (pinfunction "GND_8_AA19") (pintype "passive"))
      (node (ref "U11") (pin "AA22") (pinfunction "GND_9_AA22") (pintype "passive"))
      (node (ref "U11") (pin "AA7") (pinfunction "GND_10_AA7") (pintype "passive"))
      (node (ref "U11") (pin "AB24") (pinfunction "GND_11_AB24") (pintype "passive"))
      (node (ref "U11") (pin "AB3") (pinfunction "GND_12_AB3") (pintype "passive"))
      (node (ref "U11") (pin "AD10") (pinfunction "GND_13_AD10") (pintype "passive"))
      (node (ref "U11") (pin "AD13") (pinfunction "GND_14_AD13") (pintype "passive"))
      (node (ref "U11") (pin "AD16") (pinfunction "GND_15_AD16") (pintype "passive"))
      (node (ref "U11") (pin "AD19") (pinfunction "GND_16_AD19") (pintype "passive"))
      (node (ref "U11") (pin "AD22") (pinfunction "GND_17_AD22") (pintype "passive"))
      (node (ref "U11") (pin "AD4") (pinfunction "GND_18_AD4") (pintype "passive"))
      (node (ref "U11") (pin "AD7") (pinfunction "GND_19_AD7") (pintype "passive"))
      (node (ref "U11") (pin "AE1") (pinfunction "GND_20_AE1") (pintype "passive"))
      (node (ref "U11") (pin "AE25") (pinfunction "GND_21_AE25") (pintype "passive"))
      (node (ref "U11") (pin "B4") (pinfunction "GND_22_B4") (pintype "passive"))
      (node (ref "U11") (pin "B5") (pinfunction "VDD_FA_B5") (pintype "passive"))
      (node (ref "U11") (pin "C1") (pinfunction "GND_23_C1") (pintype "passive"))
      (node (ref "U11") (pin "C10") (pinfunction "GND_24_C10") (pintype "passive"))
      (node (ref "U11") (pin "C4") (pinfunction "GND_25_C4") (pintype "passive"))
      (node (ref "U11") (pin "C6") (pinfunction "GND_26_C6") (pintype "passive"))
      (node (ref "U11") (pin "D3") (pinfunction "GND_27_D3") (pintype "passive"))
      (node (ref "U11") (pin "D6") (pinfunction "GND_28_D6") (pintype "passive"))
      (node (ref "U11") (pin "D8") (pinfunction "GND_29_D8") (pintype "passive"))
      (node (ref "U11") (pin "E5") (pinfunction "GND_30_E5") (pintype "passive"))
      (node (ref "U11") (pin "E6") (pinfunction "GND_31_E6") (pintype "passive"))
      (node (ref "U11") (pin "E7") (pinfunction "GND_32_E7") (pintype "passive"))
      (node (ref "U11") (pin "F5") (pinfunction "GND_33_F5") (pintype "passive"))
      (node (ref "U11") (pin "F6") (pinfunction "GND_34_F6") (pintype "passive"))
      (node (ref "U11") (pin "F7") (pinfunction "GND_35_F7") (pintype "passive"))
      (node (ref "U11") (pin "F8") (pinfunction "GND_36_F8") (pintype "passive"))
      (node (ref "U11") (pin "G10") (pinfunction "GND_37_G10") (pintype "passive"))
      (node (ref "U11") (pin "G19") (pinfunction "GND_38_G19") (pintype "passive"))
      (node (ref "U11") (pin "G3") (pinfunction "GND_39_G3") (pintype "passive"))
      (node (ref "U11") (pin "H12") (pinfunction "GND_40_H12") (pintype "passive"))
      (node (ref "U11") (pin "H15") (pinfunction "GND_41_H15") (pintype "passive"))
      (node (ref "U11") (pin "H18") (pinfunction "GND_42_H18") (pintype "passive"))
      (node (ref "U11") (pin "H8") (pinfunction "GND_43_H8") (pintype "passive"))
      (node (ref "U11") (pin "J12") (pinfunction "GND_44_J12") (pintype "passive"))
      (node (ref "U11") (pin "J15") (pinfunction "GND_45_J15") (pintype "passive"))
      (node (ref "U11") (pin "J18") (pinfunction "GND_46_J18") (pintype "passive"))
      (node (ref "U11") (pin "J2") (pinfunction "GND_47_J2") (pintype "passive"))
      (node (ref "U11") (pin "J8") (pinfunction "GND_48_J8") (pintype "passive"))
      (node (ref "U11") (pin "K10") (pinfunction "GND_49_K10") (pintype "passive"))
      (node (ref "U11") (pin "K12") (pinfunction "GND_50_K12") (pintype "passive"))
      (node (ref "U11") (pin "K15") (pinfunction "GND_51_K15") (pintype "passive"))
      (node (ref "U11") (pin "K18") (pinfunction "GND_52_K18") (pintype "passive"))
      (node (ref "U11") (pin "K8") (pinfunction "GND_53_K8") (pintype "passive"))
      (node (ref "U11") (pin "L10") (pinfunction "GND_54_L10") (pintype "passive"))
      (node (ref "U11") (pin "L12") (pinfunction "GND_55_L12") (pintype "passive"))
      (node (ref "U11") (pin "L15") (pinfunction "GND_56_L15") (pintype "passive"))
      (node (ref "U11") (pin "L18") (pinfunction "GND_57_L18") (pintype "passive"))
      (node (ref "U11") (pin "L2") (pinfunction "GND_58_L2") (pintype "passive"))
      (node (ref "U11") (pin "L5") (pinfunction "GND_59_L5") (pintype "passive"))
      (node (ref "U11") (pin "L8") (pinfunction "GND_60_L8") (pintype "passive"))
      (node (ref "U11") (pin "M10") (pinfunction "GND_61_M10") (pintype "passive"))
      (node (ref "U11") (pin "M12") (pinfunction "GND_62_M12") (pintype "passive"))
      (node (ref "U11") (pin "M15") (pinfunction "GND_63_M15") (pintype "passive"))
      (node (ref "U11") (pin "M18") (pinfunction "GND_64_M18") (pintype "passive"))
      (node (ref "U11") (pin "M8") (pinfunction "GND_65_M8") (pintype "passive"))
      (node (ref "U11") (pin "N10") (pinfunction "GND_66_N10") (pintype "passive"))
      (node (ref "U11") (pin "N15") (pinfunction "GND_67_N15") (pintype "passive"))
      (node (ref "U11") (pin "N18") (pinfunction "GND_68_N18") (pintype "passive"))
      (node (ref "U11") (pin "N8") (pinfunction "GND_69_N8") (pintype "passive"))
      (node (ref "U11") (pin "P10") (pinfunction "GND_70_P10") (pintype "passive"))
      (node (ref "U11") (pin "P12") (pinfunction "GND_71_P12") (pintype "passive"))
      (node (ref "U11") (pin "P15") (pinfunction "GND_72_P15") (pintype "passive"))
      (node (ref "U11") (pin "P18") (pinfunction "GND_73_P18") (pintype "passive"))
      (node (ref "U11") (pin "P8") (pinfunction "GND_74_P8") (pintype "passive"))
      (node (ref "U11") (pin "R12") (pinfunction "GND_75_R12") (pintype "passive"))
      (node (ref "U11") (pin "R15") (pinfunction "GND_76_R15") (pintype "passive"))
      (node (ref "U11") (pin "R17") (pinfunction "GND_77_R17") (pintype "passive"))
      (node (ref "U11") (pin "R8") (pinfunction "GND_78_R8") (pintype "passive"))
      (node (ref "U11") (pin "T11") (pinfunction "GND_79_T11") (pintype "passive"))
      (node (ref "U11") (pin "T12") (pinfunction "GND_80_T12") (pintype "passive"))
      (node (ref "U11") (pin "T15") (pinfunction "GND_81_T15") (pintype "passive"))
      (node (ref "U11") (pin "T17") (pinfunction "GND_82_T17") (pintype "passive"))
      (node (ref "U11") (pin "T19") (pinfunction "GND_83_T19") (pintype "passive"))
      (node (ref "U11") (pin "T8") (pinfunction "GND_84_T8") (pintype "passive"))
      (node (ref "U11") (pin "U11") (pinfunction "GND_85_U11") (pintype "passive"))
      (node (ref "U11") (pin "U12") (pinfunction "GND_86_U12") (pintype "passive"))
      (node (ref "U11") (pin "U15") (pinfunction "GND_87_U15") (pintype "passive"))
      (node (ref "U11") (pin "U17") (pinfunction "GND_88_U17") (pintype "passive"))
      (node (ref "U11") (pin "U19") (pinfunction "GND_90_U19") (pintype "passive"))
      (node (ref "U11") (pin "U8") (pinfunction "GND_89_U8") (pintype "passive"))
      (node (ref "U11") (pin "V19") (pinfunction "GND_92_V19") (pintype "passive"))
      (node (ref "U11") (pin "V8") (pinfunction "GND_91_V8") (pintype "passive"))
      (node (ref "U11") (pin "W10") (pinfunction "GND_97_W10") (pintype "passive"))
      (node (ref "U11") (pin "W11") (pinfunction "GND_98_W11") (pintype "passive"))
      (node (ref "U11") (pin "W12") (pinfunction "GND_99_W12") (pintype "passive"))
      (node (ref "U11") (pin "W13") (pinfunction "GND_100_W13") (pintype "passive"))
      (node (ref "U11") (pin "W15") (pinfunction "GND_101_W15") (pintype "passive"))
      (node (ref "U11") (pin "W16") (pinfunction "GND_102_W16") (pintype "passive"))
      (node (ref "U11") (pin "W17") (pinfunction "GND_103_W17") (pintype "passive"))
      (node (ref "U11") (pin "W18") (pinfunction "GND_104_W18") (pintype "passive"))
      (node (ref "U11") (pin "W19") (pinfunction "GND_105_W19") (pintype "passive"))
      (node (ref "U11") (pin "W3") (pinfunction "GND_93_W3") (pintype "passive"))
      (node (ref "U11") (pin "W7") (pinfunction "GND_94_W7") (pintype "passive"))
      (node (ref "U11") (pin "W8") (pinfunction "GND_95_W8") (pintype "passive"))
      (node (ref "U11") (pin "W9") (pinfunction "GND_96_W9") (pintype "passive"))
      (node (ref "U11") (pin "Y24") (pinfunction "GND_107_Y24") (pintype "passive"))
      (node (ref "U11") (pin "Y5") (pinfunction "GND_106_Y5") (pintype "passive"))
    )
    (net (code "11") (name "Net-(U11B-NVCC_CSI)") (class "Default")
      (node (ref "C191") (pin "1") (pinfunction "1_1") (pintype "passive"))
      (node (ref "R79") (pin "1") (pinfunction "1_1") (pintype "passive"))
      (node (ref "U11") (pin "N7") (pinfunction "NVCC_CSI_N7") (pintype "passive"))
    )
    (net (code "12") (name "Net-(U11B-NVCC_ENET)") (class "Default")
      (node (ref "C181") (pin "1") (pinfunction "1_1") (pintype "passive"))
      (node (ref "C186") (pin "1") (pinfunction "1_1") (pintype "passive"))
      (node (ref "R77") (pin "1") (pinfunction "1_1") (pintype "passive"))
      (node (ref "U11") (pin "R19") (pinfunction "NVCC_ENET_R19") (pintype "passive"))
    )
    (net (code "13") (name "Net-(U11B-NVCC_MIPI)") (class "Default")
      (node (ref "C189") (pin "1") (pinfunction "1_1") (pintype "passive"))
      (node (ref "R78") (pin "1") (pinfunction "1_1") (pintype "passive"))
      (node (ref "U11") (pin "K7") (pinfunction "NVCC_MIPI_K7") (pintype "passive"))
    )
    (net (code "14") (name "Net-(U11B-NVCC_PLL_OUT)") (class "Default")
      (node (ref "C192") (pin "1") (pinfunction "1_1") (pintype "passive"))
      (node (ref "C193") (pin "1") (pinfunction "1_1") (pintype "passive"))
      (node (ref "R80") (pin "2") (pinfunction "2_2") (pintype "passive"))
      (node (ref "R81") (pin "1") (pinfunction "1_1") (pintype "passive"))
      (node (ref "R82") (pin "1") (pinfunction "1_1") (pintype "passive"))
      (node (ref "U11") (pin "E8") (pinfunction "NVCC_PLL_OUT_E8") (pintype "passive"))
    )
    (net (code "15") (name "Net-(U11B-NVCC_RGMII)") (class "Default")
      (node (ref "C167") (pin "1") (pinfunction "1_1") (pintype "passive"))
      (node (ref "R76") (pin "2") (pinfunction "2_2") (pintype "passive"))
      (node (ref "U11") (pin "G18") (pinfunction "NVCC_RGMII_G18") (pintype "passive"))
    )
    (net (code "16") (name "Net-(U11B-VDDHIGH_CAP_1)") (class "Default")
      (node (ref "C165") (pin "2") (pinfunction "2_2") (pintype "passive"))
      (node (ref "C172") (pin "1") (pinfunction "1_1") (pintype "passive"))
      (node (ref "C179") (pin "2") (pinfunction "2_2") (pintype "passive"))
      (node (ref "U11") (pin "H10") (pinfunction "VDDHIGH_CAP_1_H10") (pintype "passive"))
      (node (ref "U11") (pin "J10") (pinfunction "VDDHIGH_CAP_2_J10") (pintype "passive"))
    )
    (net (code "17") (name "Net-(U11B-VDD_SNVS_CAP)") (class "Default")
      (node (ref "C149") (pin "2") (pinfunction "2_2") (pintype "passive"))
      (node (ref "U11") (pin "G9") (pinfunction "VDD_SNVS_CAP_G9") (pintype "passive"))
    )
    (net (code "18") (name "unconnected-(U11B-GPANAIO-PadC8)") (class "Default")
      (node (ref "U11") (pin "C8") (pinfunction "GPANAIO_C8") (pintype "passive+no_connect"))
    )
  )
)
